# ARE_adaptadora_dsPIC-PIC32_28pin.net
KiCad netlist of a schematic drawn in EAGLE
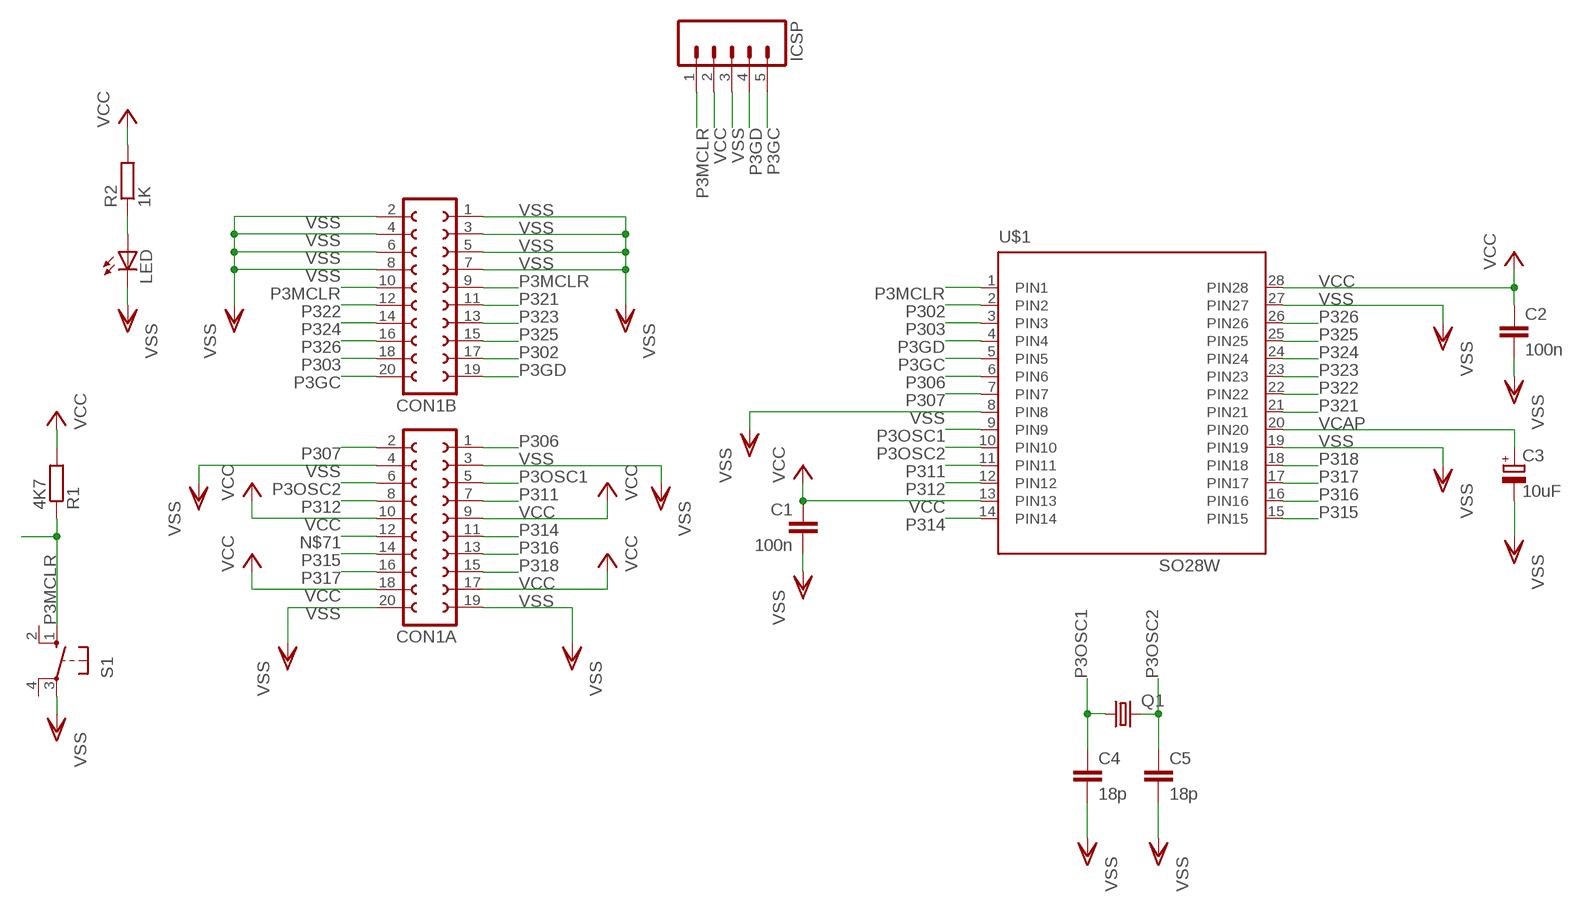
[diagram p0: schematic, sheet 1]

(export (version "E")
  (design (tool "Eeschema 10.0.6"))
  (components
    (comp (ref "C1")
      (value "100n")
      (footprint "eagle-import:C0805")
      (libsource (lib "eagle-import") (part "C-EUC0805"))
    )
    (comp (ref "C2")
      (value "100n")
      (footprint "eagle-import:C0805")
      (libsource (lib "eagle-import") (part "C-EUC0805"))
    )
    (comp (ref "C3")
      (value "10uF")
      (footprint "eagle-import:SMC_C")
      (libsource (lib "eagle-import") (part "CPOL-EUSMCC"))
    )
    (comp (ref "C4")
      (value "18p")
      (footprint "eagle-import:C0805")
      (libsource (lib "eagle-import") (part "C-EUC0805"))
    )
    (comp (ref "C5")
      (value "18p")
      (footprint "eagle-import:C0805")
      (libsource (lib "eagle-import") (part "C-EUC0805"))
    )
    (comp (ref "CON1A")
      (value "FE10-2W")
      (footprint "eagle-import:FE10-2W")
      (libsource (lib "eagle-import") (part "FE10-2W"))
    )
    (comp (ref "CON1B")
      (value "FE10-2W")
      (footprint "eagle-import:FE10-2W")
      (libsource (lib "eagle-import") (part "FE10-2W"))
    )
    (comp (ref "ICSP")
      (value "M05PTH")
      (footprint "eagle-import:1X05")
      (libsource (lib "eagle-import") (part "M05PTH"))
    )
    (comp (ref "LED")
      (value "LEDCHIPLED_0805")
      (footprint "eagle-import:CHIPLED_0805")
      (libsource (lib "eagle-import") (part "LEDCHIPLED_0805"))
    )
    (comp (ref "Q1")
      (value "CRYSTALHC18U-V")
      (footprint "eagle-import:HC18U-V")
      (libsource (lib "eagle-import") (part "CRYSTALHC18U-V"))
    )
    (comp (ref "R1")
      (value "4K7")
      (footprint "eagle-import:R0805")
      (libsource (lib "eagle-import") (part "R-EU_R0805"))
    )
    (comp (ref "R2")
      (value "1K")
      (footprint "eagle-import:R0805")
      (libsource (lib "eagle-import") (part "R-EU_R0805"))
    )
    (comp (ref "S1")
      (value "10-XX")
      (footprint "eagle-import:B3F-10XX")
      (fields
        (field (name "MPN") "B3F-1000")
        (field (name "MPN_1") "B3F-1000")
        (field (name "OC_FARNELL") "176432")
        (field (name "OC_NEWARK") "36M3542")
      )
      (libsource (lib "eagle-import") (part "10-XX"))
    )
    (comp (ref "U$1")
      (value "SO28W")
      (footprint "eagle-import:SO28W")
      (libsource (lib "eagle-import") (part "SO28W"))
    )
  )
  (nets
    (net (code "1") (name "/N$71") (class "Default")
      (node (ref "CON1A") (pin "12") (pinfunction "12_12") (pintype "passive"))
    )
    (net (code "2") (name "/P3GC") (class "Default")
      (node (ref "CON1B") (pin "20") (pinfunction "20_20") (pintype "passive"))
      (node (ref "ICSP") (pin "5") (pinfunction "5_5") (pintype "passive"))
      (node (ref "U$1") (pin "5") (pinfunction "PIN5_5") (pintype "input"))
    )
    (net (code "3") (name "/P3GD") (class "Default")
      (node (ref "CON1B") (pin "19") (pinfunction "19_19") (pintype "passive"))
      (node (ref "ICSP") (pin "4") (pinfunction "4_4") (pintype "passive"))
      (node (ref "U$1") (pin "4") (pinfunction "PIN4_4") (pintype "input"))
    )
    (net (code "4") (name "/P3MCLR") (class "Default")
      (node (ref "CON1B") (pin "10") (pinfunction "10_10") (pintype "passive"))
      (node (ref "CON1B") (pin "9") (pinfunction "9_9") (pintype "passive"))
      (node (ref "ICSP") (pin "1") (pinfunction "1_1") (pintype "passive"))
      (node (ref "R1") (pin "1") (pinfunction "1_1") (pintype "passive"))
      (node (ref "S1") (pin "1") (pinfunction "S_1") (pintype "passive"))
      (node (ref "U$1") (pin "1") (pinfunction "PIN1_1") (pintype "input"))
    )
    (net (code "5") (name "/P3OSC1") (class "Default")
      (node (ref "C4") (pin "1") (pinfunction "1_1") (pintype "passive"))
      (node (ref "CON1A") (pin "5") (pinfunction "5_5") (pintype "passive"))
      (node (ref "Q1") (pin "1") (pinfunction "1_1") (pintype "passive"))
      (node (ref "U$1") (pin "9") (pinfunction "PIN9_9") (pintype "input"))
    )
    (net (code "6") (name "/P3OSC2") (class "Default")
      (node (ref "C5") (pin "1") (pinfunction "1_1") (pintype "passive"))
      (node (ref "CON1A") (pin "6") (pinfunction "6_6") (pintype "passive"))
      (node (ref "Q1") (pin "2") (pinfunction "2_2") (pintype "passive"))
      (node (ref "U$1") (pin "10") (pinfunction "PIN10_10") (pintype "input"))
    )
    (net (code "7") (name "/P302") (class "Default")
      (node (ref "CON1B") (pin "17") (pinfunction "17_17") (pintype "passive"))
      (node (ref "U$1") (pin "2") (pinfunction "PIN2_2") (pintype "input"))
    )
    (net (code "8") (name "/P303") (class "Default")
      (node (ref "CON1B") (pin "18") (pinfunction "18_18") (pintype "passive"))
      (node (ref "U$1") (pin "3") (pinfunction "PIN3_3") (pintype "input"))
    )
    (net (code "9") (name "/P306") (class "Default")
      (node (ref "CON1A") (pin "1") (pinfunction "1_1") (pintype "passive"))
      (node (ref "U$1") (pin "6") (pinfunction "PIN6_6") (pintype "input"))
    )
    (net (code "10") (name "/P307") (class "Default")
      (node (ref "CON1A") (pin "2") (pinfunction "2_2") (pintype "passive"))
      (node (ref "U$1") (pin "7") (pinfunction "PIN7_7") (pintype "input"))
    )
    (net (code "11") (name "/P311") (class "Default")
      (node (ref "CON1A") (pin "7") (pinfunction "7_7") (pintype "passive"))
      (node (ref "U$1") (pin "11") (pinfunction "PIN11_11") (pintype "input"))
    )
    (net (code "12") (name "/P312") (class "Default")
      (node (ref "CON1A") (pin "8") (pinfunction "8_8") (pintype "passive"))
      (node (ref "U$1") (pin "12") (pinfunction "PIN12_12") (pintype "input"))
    )
    (net (code "13") (name "/P314") (class "Default")
      (node (ref "CON1A") (pin "11") (pinfunction "11_11") (pintype "passive"))
      (node (ref "U$1") (pin "14") (pinfunction "PIN14_14") (pintype "input"))
    )
    (net (code "14") (name "/P315") (class "Default")
      (node (ref "CON1A") (pin "14") (pinfunction "14_14") (pintype "passive"))
      (node (ref "U$1") (pin "15") (pinfunction "PIN15_15") (pintype "input"))
    )
    (net (code "15") (name "/P316") (class "Default")
      (node (ref "CON1A") (pin "13") (pinfunction "13_13") (pintype "passive"))
      (node (ref "U$1") (pin "16") (pinfunction "PIN16_16") (pintype "input"))
    )
    (net (code "16") (name "/P317") (class "Default")
      (node (ref "CON1A") (pin "16") (pinfunction "16_16") (pintype "passive"))
      (node (ref "U$1") (pin "17") (pinfunction "PIN17_17") (pintype "input"))
    )
    (net (code "17") (name "/P318") (class "Default")
      (node (ref "CON1A") (pin "15") (pinfunction "15_15") (pintype "passive"))
      (node (ref "U$1") (pin "18") (pinfunction "PIN18_18") (pintype "input"))
    )
    (net (code "18") (name "/P321") (class "Default")
      (node (ref "CON1B") (pin "11") (pinfunction "11_11") (pintype "passive"))
      (node (ref "U$1") (pin "21") (pinfunction "PIN21_21") (pintype "input"))
    )
    (net (code "19") (name "/P322") (class "Default")
      (node (ref "CON1B") (pin "12") (pinfunction "12_12") (pintype "passive"))
      (node (ref "U$1") (pin "22") (pinfunction "PIN22_22") (pintype "input"))
    )
    (net (code "20") (name "/P323") (class "Default")
      (node (ref "CON1B") (pin "13") (pinfunction "13_13") (pintype "passive"))
      (node (ref "U$1") (pin "23") (pinfunction "PIN23_23") (pintype "input"))
    )
    (net (code "21") (name "/P324") (class "Default")
      (node (ref "CON1B") (pin "14") (pinfunction "14_14") (pintype "passive"))
      (node (ref "U$1") (pin "24") (pinfunction "PIN24_24") (pintype "input"))
    )
    (net (code "22") (name "/P325") (class "Default")
      (node (ref "CON1B") (pin "15") (pinfunction "15_15") (pintype "passive"))
      (node (ref "U$1") (pin "25") (pinfunction "PIN25_25") (pintype "input"))
    )
    (net (code "23") (name "/P326") (class "Default")
      (node (ref "CON1B") (pin "16") (pinfunction "16_16") (pintype "passive"))
      (node (ref "U$1") (pin "26") (pinfunction "PIN26_26") (pintype "input"))
    )
    (net (code "24") (name "/VCAP") (class "Default")
      (node (ref "C3") (pin "+") (pinfunction "+_+") (pintype "passive"))
      (node (ref "U$1") (pin "20") (pinfunction "PIN20_20") (pintype "input"))
    )
    (net (code "25") (name "Net-(LED-PadA)") (class "Default")
      (node (ref "LED") (pin "A") (pinfunction "A_A") (pintype "passive"))
      (node (ref "R2") (pin "1") (pinfunction "1_1") (pintype "passive"))
    )
    (net (code "26") (name "VCC") (class "Default")
      (node (ref "C1") (pin "1") (pinfunction "1_1") (pintype "passive"))
      (node (ref "C2") (pin "1") (pinfunction "1_1") (pintype "passive"))
      (node (ref "CON1A") (pin "10") (pinfunction "10_10") (pintype "passive"))
      (node (ref "CON1A") (pin "17") (pinfunction "17_17") (pintype "passive"))
      (node (ref "CON1A") (pin "18") (pinfunction "18_18") (pintype "passive"))
      (node (ref "CON1A") (pin "9") (pinfunction "9_9") (pintype "passive"))
      (node (ref "ICSP") (pin "2") (pinfunction "2_2") (pintype "passive"))
      (node (ref "R1") (pin "2") (pinfunction "2_2") (pintype "passive"))
      (node (ref "R2") (pin "2") (pinfunction "2_2") (pintype "passive"))
      (node (ref "U$1") (pin "13") (pinfunction "PIN13_13") (pintype "input"))
      (node (ref "U$1") (pin "28") (pinfunction "PIN28_28") (pintype "input"))
    )
    (net (code "27") (name "VSS") (class "Default")
      (node (ref "C1") (pin "2") (pinfunction "2_2") (pintype "passive"))
      (node (ref "C2") (pin "2") (pinfunction "2_2") (pintype "passive"))
      (node (ref "C3") (pin "-") (pinfunction "-_-") (pintype "passive"))
      (node (ref "C4") (pin "2") (pinfunction "2_2") (pintype "passive"))
      (node (ref "C5") (pin "2") (pinfunction "2_2") (pintype "passive"))
      (node (ref "CON1A") (pin "19") (pinfunction "19_19") (pintype "passive"))
      (node (ref "CON1A") (pin "20") (pinfunction "20_20") (pintype "passive"))
      (node (ref "CON1A") (pin "3") (pinfunction "3_3") (pintype "passive"))
      (node (ref "CON1A") (pin "4") (pinfunction "4_4") (pintype "passive"))
      (node (ref "CON1B") (pin "1") (pinfunction "1_1") (pintype "passive"))
      (node (ref "CON1B") (pin "2") (pinfunction "2_2") (pintype "passive"))
      (node (ref "CON1B") (pin "3") (pinfunction "3_3") (pintype "passive"))
      (node (ref "CON1B") (pin "4") (pinfunction "4_4") (pintype "passive"))
      (node (ref "CON1B") (pin "5") (pinfunction "5_5") (pintype "passive"))
      (node (ref "CON1B") (pin "6") (pinfunction "6_6") (pintype "passive"))
      (node (ref "CON1B") (pin "7") (pinfunction "7_7") (pintype "passive"))
      (node (ref "CON1B") (pin "8") (pinfunction "8_8") (pintype "passive"))
      (node (ref "ICSP") (pin "3") (pinfunction "3_3") (pintype "passive"))
      (node (ref "LED") (pin "C") (pinfunction "C_C") (pintype "passive"))
      (node (ref "S1") (pin "3") (pinfunction "P_3") (pintype "passive"))
      (node (ref "U$1") (pin "19") (pinfunction "PIN19_19") (pintype "input"))
      (node (ref "U$1") (pin "27") (pinfunction "PIN27_27") (pintype "input"))
      (node (ref "U$1") (pin "8") (pinfunction "PIN8_8") (pintype "input"))
    )
    (net (code "28") (name "unconnected-(S1-P1-Pad4)") (class "Default")
      (node (ref "S1") (pin "4") (pinfunction "P1_4") (pintype "passive"))
    )
    (net (code "29") (name "unconnected-(S1-S1-Pad2)") (class "Default")
      (node (ref "S1") (pin "2") (pinfunction "S1_2") (pintype "passive"))
    )
  )
)
